# D_D_dice_1.net
KiCad netlist of a schematic drawn in EAGLE
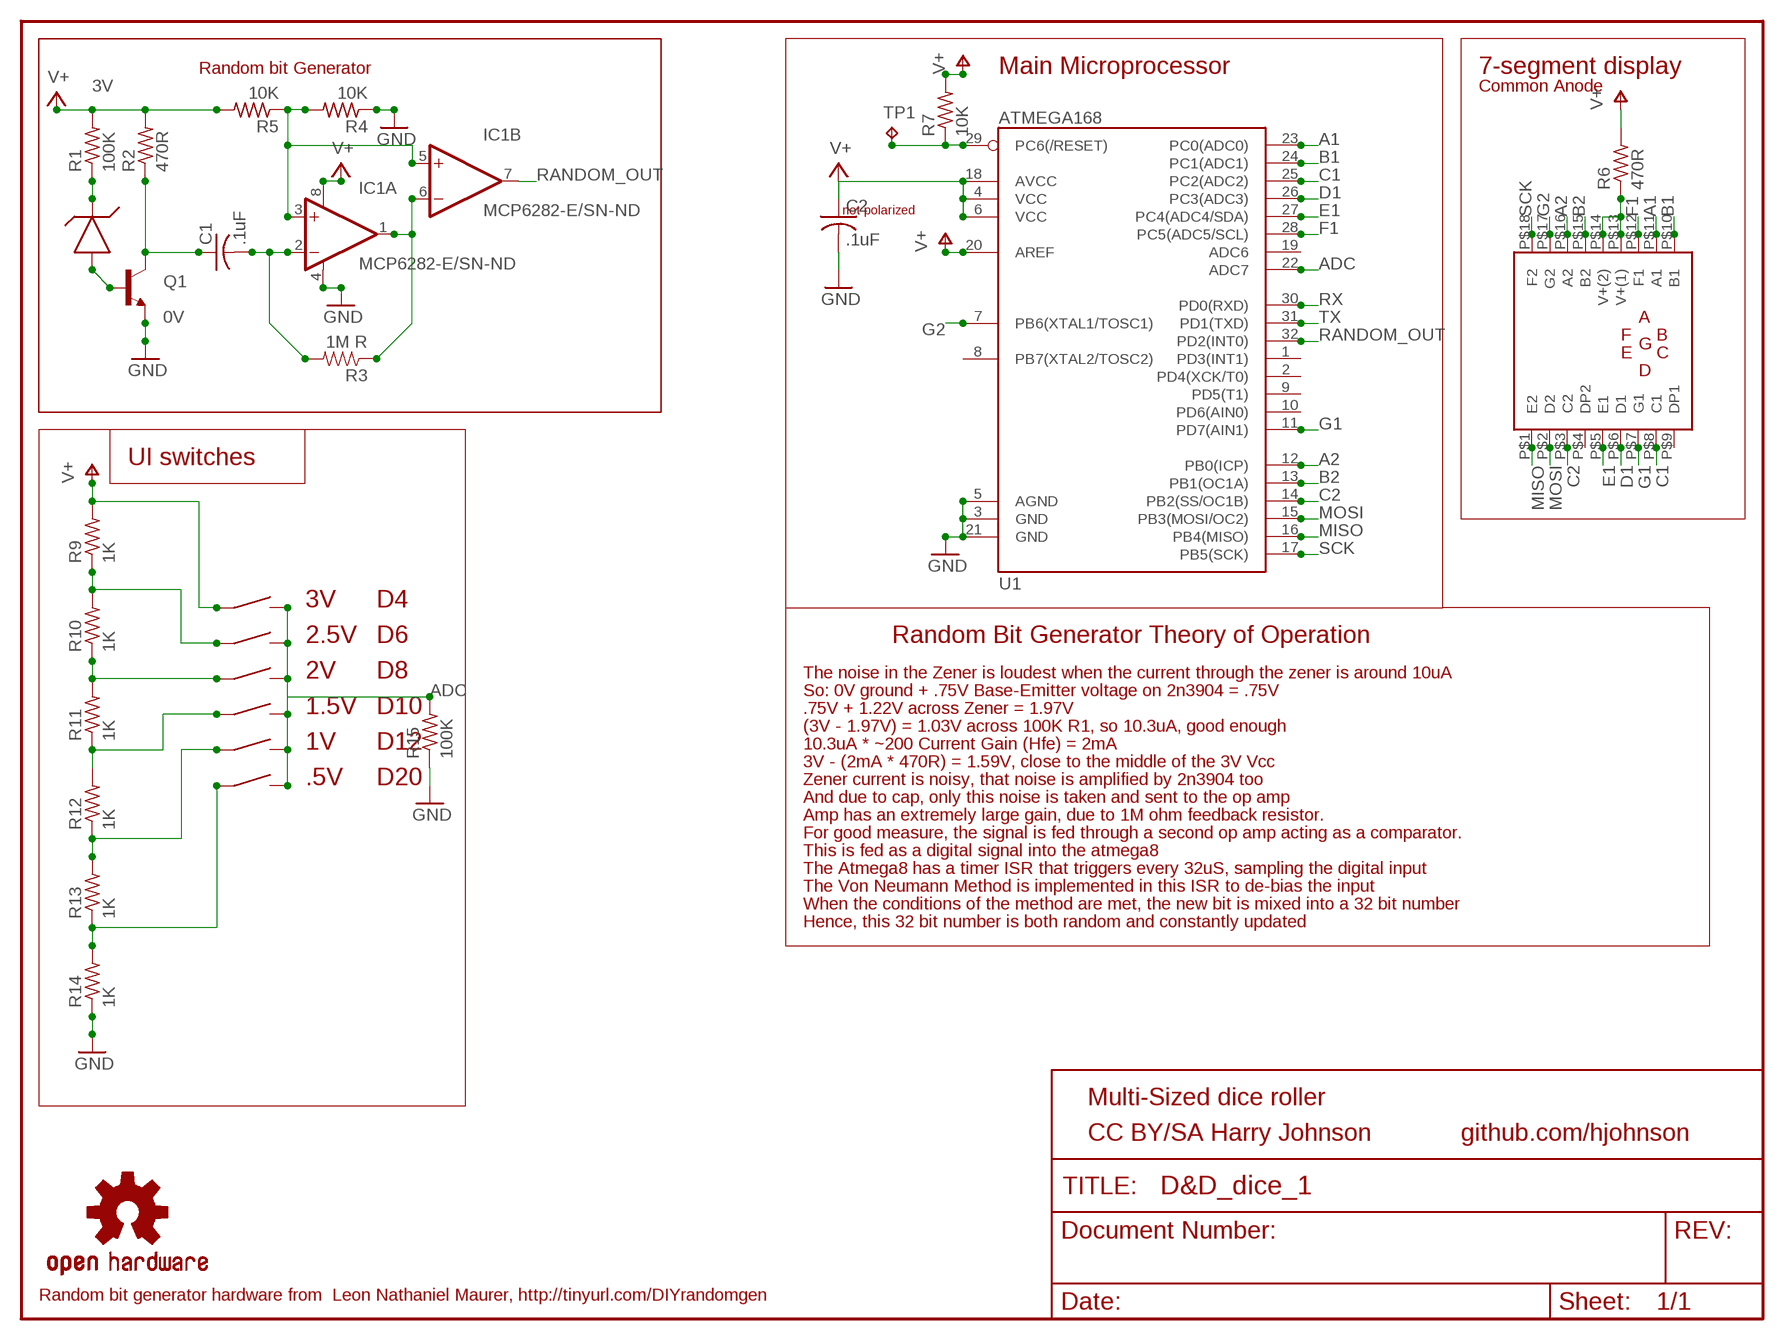
[diagram p0: schematic, sheet 1]

(export (version "E")
  (design (tool "Eeschema 10.0.6"))
  (components
    (comp (ref "C1")
      (value ".1uF")
      (footprint "eagle-import:C0805")
      (libsource (lib "eagle-import") (part "C-USC0805"))
    )
    (comp (ref "C2")
      (value ".1uF")
      (footprint "eagle-import:C0805")
      (libsource (lib "eagle-import") (part "C-USC0805"))
    )
    (comp (ref "IC1")
      (value "MCP6282-E/SN-ND")
      (footprint "eagle-import:SO08")
      (fields (field (name "MF") "TEXAS INSTRUMENTS") (field (name "MPN") "OPA2340UA"))
      (libsource (lib "eagle-import") (part "OPA2340U"))
    )
    (comp (ref "Q1")
      (value "TRANSISTOR_NPNSOT23")
      (footprint "eagle-import:SOT23")
      (libsource (lib "eagle-import") (part "TRANSISTOR_NPNSOT23"))
    )
    (comp (ref "R1")
      (value "100K")
      (footprint "eagle-import:R0805")
      (libsource (lib "eagle-import") (part "R-US_R0805"))
    )
    (comp (ref "R2")
      (value "470R")
      (footprint "eagle-import:R0805")
      (libsource (lib "eagle-import") (part "R-US_R0805"))
    )
    (comp (ref "R3")
      (value "1M R")
      (footprint "eagle-import:0805")
      (libsource (lib "eagle-import") (part "RESISTOR0805-RES"))
    )
    (comp (ref "R4")
      (value "10K")
      (footprint "eagle-import:R0805")
      (libsource (lib "eagle-import") (part "R-US_R0805"))
    )
    (comp (ref "R5")
      (value "10K")
      (footprint "eagle-import:R0805")
      (libsource (lib "eagle-import") (part "R-US_R0805"))
    )
    (comp (ref "R6")
      (value "470R")
      (footprint "eagle-import:R0805")
      (libsource (lib "eagle-import") (part "R-US_R0805"))
    )
    (comp (ref "R7")
      (value "10K")
      (footprint "eagle-import:R0805")
      (libsource (lib "eagle-import") (part "R-US_R0805"))
    )
    (comp (ref "R9")
      (value "1K")
      (footprint "eagle-import:R0805")
      (libsource (lib "eagle-import") (part "R-US_R0805"))
    )
    (comp (ref "R10")
      (value "1K")
      (footprint "eagle-import:R0805")
      (libsource (lib "eagle-import") (part "R-US_R0805"))
    )
    (comp (ref "R11")
      (value "1K")
      (footprint "eagle-import:R0805")
      (libsource (lib "eagle-import") (part "R-US_R0805"))
    )
    (comp (ref "R12")
      (value "1K")
      (footprint "eagle-import:R0805")
      (libsource (lib "eagle-import") (part "R-US_R0805"))
    )
    (comp (ref "R13")
      (value "1K")
      (footprint "eagle-import:R0805")
      (libsource (lib "eagle-import") (part "R-US_R0805"))
    )
    (comp (ref "R14")
      (value "1K")
      (footprint "eagle-import:R0805")
      (libsource (lib "eagle-import") (part "R-US_R0805"))
    )
    (comp (ref "R15")
      (value "100K")
      (footprint "eagle-import:R0805")
      (libsource (lib "eagle-import") (part "R-US_R0805"))
    )
    (comp (ref "SW1")
      (value "SPST_SWITCH")
      (footprint "eagle-import:EG2513-ND")
      (libsource (lib "eagle-import") (part "SPST_SWITCH"))
    )
    (comp (ref "SW2")
      (value "SPST_SWITCH")
      (footprint "eagle-import:EG2513-ND")
      (libsource (lib "eagle-import") (part "SPST_SWITCH"))
    )
    (comp (ref "SW3")
      (value "SPST_SWITCH")
      (footprint "eagle-import:EG2513-ND")
      (libsource (lib "eagle-import") (part "SPST_SWITCH"))
    )
    (comp (ref "SW4")
      (value "SPST_SWITCH")
      (footprint "eagle-import:EG2513-ND")
      (libsource (lib "eagle-import") (part "SPST_SWITCH"))
    )
    (comp (ref "SW5")
      (value "SPST_SWITCH")
      (footprint "eagle-import:EG2513-ND")
      (libsource (lib "eagle-import") (part "SPST_SWITCH"))
    )
    (comp (ref "SW6")
      (value "SPST_SWITCH")
      (footprint "eagle-import:EG2513-ND")
      (libsource (lib "eagle-import") (part "SPST_SWITCH"))
    )
    (comp (ref "TP1")
      (value "TPB1,27")
      (footprint "eagle-import:B1,27")
      (libsource (lib "eagle-import") (part "TPB1,27"))
    )
    (comp (ref "U$1")
      (value "ZXRE1004FFTA")
      (footprint "eagle-import:SOT23")
      (libsource (lib "eagle-import") (part "ZXRE1004FFTA"))
    )
    (comp (ref "U$2")
      (value "2DIGIT_7SEGMENT")
      (footprint "eagle-import:HDSP-521E")
      (libsource (lib "eagle-import") (part "2DIGIT_7SEGMENT"))
    )
    (comp (ref "U$3")
      (value "OSHW-LOGOS")
      (footprint "eagle-import:OSHW-LOGO-S")
      (libsource (lib "eagle-import") (part "OSHW-LOGOS"))
    )
    (comp (ref "U1")
      (value "ATMEGA168")
      (footprint "eagle-import:TQFP32-08")
      (libsource (lib "eagle-import") (part "ATMEGA168"))
    )
  )
  (nets
    (net (code "1") (name "/A1") (class "Default")
      (node (ref "U$2") (pin "P$11") (pinfunction "A1_P$11") (pintype "bidirectional"))
      (node (ref "U1") (pin "23") (pinfunction "PC0(ADC0)_23") (pintype "bidirectional"))
    )
    (net (code "2") (name "/A2") (class "Default")
      (node (ref "U$2") (pin "P$16") (pinfunction "A2_P$16") (pintype "bidirectional"))
      (node (ref "U1") (pin "12") (pinfunction "PB0(ICP)_12") (pintype "bidirectional"))
    )
    (net (code "3") (name "/ADC") (class "Default")
      (node (ref "R15") (pin "2") (pinfunction "2_2") (pintype "passive"))
      (node (ref "SW1") (pin "P$2") (pinfunction "2_P$2") (pintype "bidirectional"))
      (node (ref "SW2") (pin "P$2") (pinfunction "2_P$2") (pintype "bidirectional"))
      (node (ref "SW3") (pin "P$2") (pinfunction "2_P$2") (pintype "bidirectional"))
      (node (ref "SW4") (pin "P$2") (pinfunction "2_P$2") (pintype "bidirectional"))
      (node (ref "SW5") (pin "P$2") (pinfunction "2_P$2") (pintype "bidirectional"))
      (node (ref "SW6") (pin "P$2") (pinfunction "2_P$2") (pintype "bidirectional"))
      (node (ref "U1") (pin "22") (pinfunction "ADC7_22") (pintype "bidirectional"))
    )
    (net (code "4") (name "/B1") (class "Default")
      (node (ref "U$2") (pin "P$10") (pinfunction "B1_P$10") (pintype "bidirectional"))
      (node (ref "U1") (pin "24") (pinfunction "PC1(ADC1)_24") (pintype "bidirectional"))
    )
    (net (code "5") (name "/B2") (class "Default")
      (node (ref "U$2") (pin "P$15") (pinfunction "B2_P$15") (pintype "bidirectional"))
      (node (ref "U1") (pin "13") (pinfunction "PB1(OC1A)_13") (pintype "bidirectional"))
    )
    (net (code "6") (name "/C1") (class "Default")
      (node (ref "U$2") (pin "P$8") (pinfunction "C1_P$8") (pintype "bidirectional"))
      (node (ref "U1") (pin "25") (pinfunction "PC2(ADC2)_25") (pintype "bidirectional"))
    )
    (net (code "7") (name "/C2") (class "Default")
      (node (ref "U$2") (pin "P$3") (pinfunction "C2_P$3") (pintype "bidirectional"))
      (node (ref "U1") (pin "14") (pinfunction "PB2(SS/OC1B)_14") (pintype "bidirectional"))
    )
    (net (code "8") (name "/D1") (class "Default")
      (node (ref "U$2") (pin "P$6") (pinfunction "D1_P$6") (pintype "bidirectional"))
      (node (ref "U1") (pin "26") (pinfunction "PC3(ADC3)_26") (pintype "bidirectional"))
    )
    (net (code "9") (name "/E1") (class "Default")
      (node (ref "U$2") (pin "P$5") (pinfunction "E1_P$5") (pintype "bidirectional"))
      (node (ref "U1") (pin "27") (pinfunction "PC4(ADC4/SDA)_27") (pintype "bidirectional"))
    )
    (net (code "10") (name "/F1") (class "Default")
      (node (ref "U$2") (pin "P$12") (pinfunction "F1_P$12") (pintype "bidirectional"))
      (node (ref "U1") (pin "28") (pinfunction "PC5(ADC5/SCL)_28") (pintype "bidirectional"))
    )
    (net (code "11") (name "/G1") (class "Default")
      (node (ref "U$2") (pin "P$7") (pinfunction "G1_P$7") (pintype "bidirectional"))
      (node (ref "U1") (pin "11") (pinfunction "PD7(AIN1)_11") (pintype "bidirectional"))
    )
    (net (code "12") (name "/G2") (class "Default")
      (node (ref "U$2") (pin "P$17") (pinfunction "G2_P$17") (pintype "bidirectional"))
      (node (ref "U1") (pin "7") (pinfunction "PB6(XTAL1/TOSC1)_7") (pintype "bidirectional"))
    )
    (net (code "13") (name "/MISO") (class "Default")
      (node (ref "U$2") (pin "P$1") (pinfunction "E2_P$1") (pintype "bidirectional"))
      (node (ref "U1") (pin "16") (pinfunction "PB4(MISO)_16") (pintype "bidirectional"))
    )
    (net (code "14") (name "/MOSI") (class "Default")
      (node (ref "U$2") (pin "P$2") (pinfunction "D2_P$2") (pintype "bidirectional"))
      (node (ref "U1") (pin "15") (pinfunction "PB3(MOSI/OC2)_15") (pintype "bidirectional"))
    )
    (net (code "15") (name "/RANDOM_OUT") (class "Default")
      (node (ref "IC1") (pin "7") (pinfunction "OUT_7") (pintype "output"))
      (node (ref "U1") (pin "32") (pinfunction "PD2(INT0)_32") (pintype "bidirectional"))
    )
    (net (code "16") (name "/RX") (class "Default")
      (node (ref "U1") (pin "30") (pinfunction "PD0(RXD)_30") (pintype "bidirectional"))
    )
    (net (code "17") (name "/SCK") (class "Default")
      (node (ref "U$2") (pin "P$18") (pinfunction "F2_P$18") (pintype "bidirectional"))
      (node (ref "U1") (pin "17") (pinfunction "PB5(SCK)_17") (pintype "bidirectional"))
    )
    (net (code "18") (name "/TX") (class "Default")
      (node (ref "U1") (pin "31") (pinfunction "PD1(TXD)_31") (pintype "bidirectional"))
    )
    (net (code "19") (name "GND") (class "Default")
      (node (ref "C2") (pin "2") (pinfunction "2_2") (pintype "passive"))
      (node (ref "IC1") (pin "4") (pinfunction "V-_4") (pintype "power_in"))
      (node (ref "Q1") (pin "2") (pinfunction "E_2") (pintype "passive"))
      (node (ref "R14") (pin "1") (pinfunction "1_1") (pintype "passive"))
      (node (ref "R15") (pin "1") (pinfunction "1_1") (pintype "passive"))
      (node (ref "R4") (pin "1") (pinfunction "1_1") (pintype "passive"))
      (node (ref "U1") (pin "21") (pinfunction "GND_21") (pintype "bidirectional"))
      (node (ref "U1") (pin "3") (pinfunction "GND_3") (pintype "bidirectional"))
      (node (ref "U1") (pin "5") (pinfunction "AGND_5") (pintype "bidirectional"))
    )
    (net (code "20") (name "Net-(IC1A-+IN)") (class "Default")
      (node (ref "IC1") (pin "3") (pinfunction "+IN_3") (pintype "input"))
      (node (ref "IC1") (pin "5") (pinfunction "+IN_5") (pintype "input"))
      (node (ref "R4") (pin "2") (pinfunction "2_2") (pintype "passive"))
      (node (ref "R5") (pin "1") (pinfunction "1_1") (pintype "passive"))
    )
    (net (code "21") (name "Net-(IC1A--IN)") (class "Default")
      (node (ref "C1") (pin "2") (pinfunction "2_2") (pintype "passive"))
      (node (ref "IC1") (pin "2") (pinfunction "-IN_2") (pintype "input"))
      (node (ref "R3") (pin "2") (pinfunction "2_2") (pintype "passive"))
    )
    (net (code "22") (name "Net-(IC1A-OUT)") (class "Default")
      (node (ref "IC1") (pin "1") (pinfunction "OUT_1") (pintype "output"))
      (node (ref "IC1") (pin "6") (pinfunction "-IN_6") (pintype "input"))
      (node (ref "R3") (pin "1") (pinfunction "1_1") (pintype "passive"))
    )
    (net (code "23") (name "Net-(Q1-B)") (class "Default")
      (node (ref "Q1") (pin "1") (pinfunction "B_1") (pintype "passive"))
      (node (ref "U$1") (pin "2") (pinfunction "A_2") (pintype "bidirectional"))
    )
    (net (code "24") (name "Net-(Q1-C)") (class "Default")
      (node (ref "C1") (pin "1") (pinfunction "1_1") (pintype "passive"))
      (node (ref "Q1") (pin "3") (pinfunction "C_3") (pintype "passive"))
      (node (ref "R2") (pin "1") (pinfunction "1_1") (pintype "passive"))
    )
    (net (code "25") (name "Net-(SW2-1)") (class "Default")
      (node (ref "R10") (pin "2") (pinfunction "2_2") (pintype "passive"))
      (node (ref "R9") (pin "1") (pinfunction "1_1") (pintype "passive"))
      (node (ref "SW2") (pin "P$1") (pinfunction "1_P$1") (pintype "bidirectional"))
    )
    (net (code "26") (name "Net-(SW3-1)") (class "Default")
      (node (ref "R10") (pin "1") (pinfunction "1_1") (pintype "passive"))
      (node (ref "R11") (pin "2") (pinfunction "2_2") (pintype "passive"))
      (node (ref "SW3") (pin "P$1") (pinfunction "1_P$1") (pintype "bidirectional"))
    )
    (net (code "27") (name "Net-(SW4-1)") (class "Default")
      (node (ref "R11") (pin "1") (pinfunction "1_1") (pintype "passive"))
      (node (ref "R12") (pin "2") (pinfunction "2_2") (pintype "passive"))
      (node (ref "SW4") (pin "P$1") (pinfunction "1_P$1") (pintype "bidirectional"))
    )
    (net (code "28") (name "Net-(SW5-1)") (class "Default")
      (node (ref "R12") (pin "1") (pinfunction "1_1") (pintype "passive"))
      (node (ref "R13") (pin "2") (pinfunction "2_2") (pintype "passive"))
      (node (ref "SW5") (pin "P$1") (pinfunction "1_P$1") (pintype "bidirectional"))
    )
    (net (code "29") (name "Net-(SW6-1)") (class "Default")
      (node (ref "R13") (pin "1") (pinfunction "1_1") (pintype "passive"))
      (node (ref "R14") (pin "2") (pinfunction "2_2") (pintype "passive"))
      (node (ref "SW6") (pin "P$1") (pinfunction "1_P$1") (pintype "bidirectional"))
    )
    (net (code "30") (name "Net-(U$1-K)") (class "Default")
      (node (ref "R1") (pin "1") (pinfunction "1_1") (pintype "passive"))
      (node (ref "U$1") (pin "1") (pinfunction "K_1") (pintype "bidirectional"))
    )
    (net (code "31") (name "Net-(U$2-V+(1))") (class "Default")
      (node (ref "R6") (pin "1") (pinfunction "1_1") (pintype "passive"))
      (node (ref "U$2") (pin "P$13") (pinfunction "V+(1)_P$13") (pintype "bidirectional"))
      (node (ref "U$2") (pin "P$14") (pinfunction "V+(2)_P$14") (pintype "bidirectional"))
    )
    (net (code "32") (name "Net-(U1-PC6({slash}RESET))") (class "Default")
      (node (ref "R7") (pin "1") (pinfunction "1_1") (pintype "passive"))
      (node (ref "TP1") (pin "TP") (pinfunction "TP_TP") (pintype "input"))
      (node (ref "U1") (pin "29") (pinfunction "PC6(/RESET)_29") (pintype "bidirectional"))
    )
    (net (code "33") (name "V+") (class "Default")
      (node (ref "C2") (pin "1") (pinfunction "1_1") (pintype "passive"))
      (node (ref "IC1") (pin "8") (pinfunction "V+_8") (pintype "power_in"))
      (node (ref "R1") (pin "2") (pinfunction "2_2") (pintype "passive"))
      (node (ref "R2") (pin "2") (pinfunction "2_2") (pintype "passive"))
      (node (ref "R5") (pin "2") (pinfunction "2_2") (pintype "passive"))
      (node (ref "R6") (pin "2") (pinfunction "2_2") (pintype "passive"))
      (node (ref "R7") (pin "2") (pinfunction "2_2") (pintype "passive"))
      (node (ref "R9") (pin "2") (pinfunction "2_2") (pintype "passive"))
      (node (ref "SW1") (pin "P$1") (pinfunction "1_P$1") (pintype "bidirectional"))
      (node (ref "U1") (pin "18") (pinfunction "AVCC_18") (pintype "bidirectional"))
      (node (ref "U1") (pin "20") (pinfunction "AREF_20") (pintype "bidirectional"))
      (node (ref "U1") (pin "4") (pinfunction "VCC_4") (pintype "bidirectional"))
      (node (ref "U1") (pin "6") (pinfunction "VCC_6") (pintype "bidirectional"))
    )
    (net (code "34") (name "unconnected-(U$2-DP1-PadP$9)") (class "Default")
      (node (ref "U$2") (pin "P$9") (pinfunction "DP1_P$9") (pintype "bidirectional"))
    )
    (net (code "35") (name "unconnected-(U$2-DP2-PadP$4)") (class "Default")
      (node (ref "U$2") (pin "P$4") (pinfunction "DP2_P$4") (pintype "bidirectional"))
    )
    (net (code "36") (name "unconnected-(U1-ADC6-Pad19)") (class "Default")
      (node (ref "U1") (pin "19") (pinfunction "ADC6_19") (pintype "bidirectional"))
    )
    (net (code "37") (name "unconnected-(U1-PB7(XTAL2{slash}TOSC2)-Pad8)") (class "Default")
      (node (ref "U1") (pin "8") (pinfunction "PB7(XTAL2/TOSC2)_8") (pintype "bidirectional"))
    )
    (net (code "38") (name "unconnected-(U1-PD3(INT1)-Pad1)") (class "Default")
      (node (ref "U1") (pin "1") (pinfunction "PD3(INT1)_1") (pintype "bidirectional"))
    )
    (net (code "39") (name "unconnected-(U1-PD4(XCK{slash}T0)-Pad2)") (class "Default")
      (node (ref "U1") (pin "2") (pinfunction "PD4(XCK/T0)_2") (pintype "bidirectional"))
    )
    (net (code "40") (name "unconnected-(U1-PD5(T1)-Pad9)") (class "Default")
      (node (ref "U1") (pin "9") (pinfunction "PD5(T1)_9") (pintype "bidirectional"))
    )
    (net (code "41") (name "unconnected-(U1-PD6(AIN0)-Pad10)") (class "Default")
      (node (ref "U1") (pin "10") (pinfunction "PD6(AIN0)_10") (pintype "bidirectional"))
    )
  )
)
